# yard-ice-fpga.net
KiCad netlist of a schematic drawn in Altium Designer
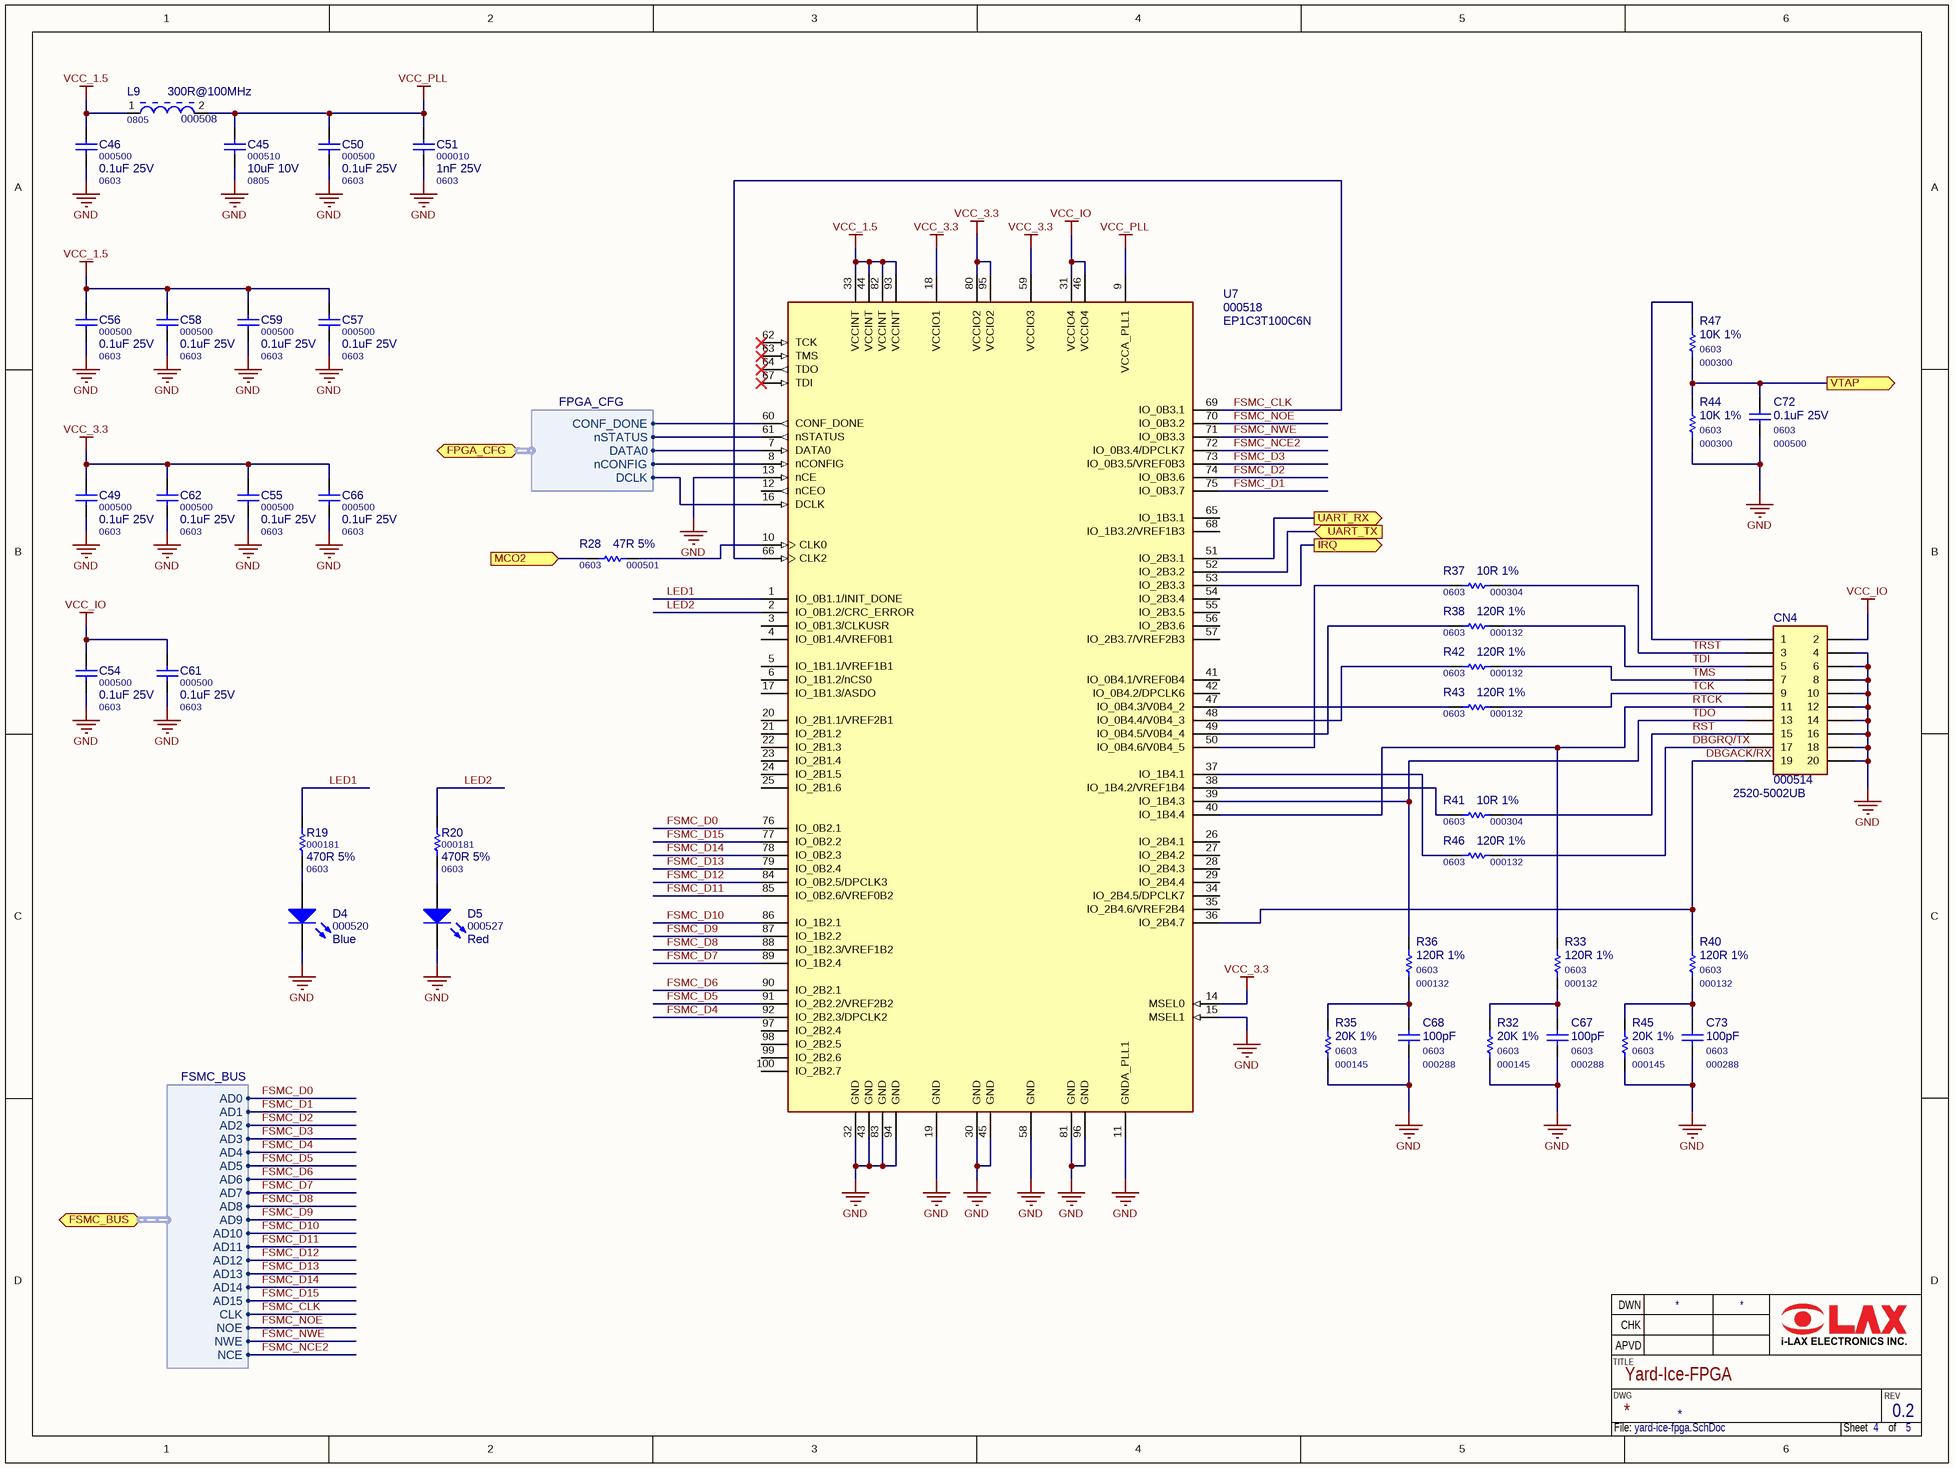
[diagram p0: yard-ice-fpga.SchDoc]

(export (version "E")
  (design (tool "Eeschema 10.0.6"))
  (components
    (comp (ref "C45")
      (value "000510")
      (footprint "C0805M")
      (description "SMD Ceramic Chip Capacitor - 0805 - X7R")
      (fields
        (field (name "ALTIUM_VALUE") "10uF 10V")
        (field (name "PACKAGE") "0805")
        (field (name "MF") "TDK")
      )
      (libsource (lib "discrete-sm") (part "C0805"))
    )
    (comp (ref "C46")
      (value "000500")
      (footprint "C0603M")
      (description "SMD Ceramic Chip Capacitor - 0603 - X7R")
      (fields
        (field (name "ALTIUM_VALUE") "0.1uF 25V")
        (field (name "PACKAGE") "0603")
        (field (name "MF") "TDK")
      )
      (libsource (lib "discrete-sm") (part "C0603"))
    )
    (comp (ref "C49")
      (value "000500")
      (footprint "C0603M")
      (description "SMD Ceramic Chip Capacitor - 0603 - X7R")
      (fields
        (field (name "ALTIUM_VALUE") "0.1uF 25V")
        (field (name "PACKAGE") "0603")
        (field (name "MF") "TDK")
      )
      (libsource (lib "discrete-sm") (part "C0603"))
    )
    (comp (ref "C50")
      (value "000500")
      (footprint "C0603M")
      (description "SMD Ceramic Chip Capacitor - 0603 - X7R")
      (fields
        (field (name "ALTIUM_VALUE") "0.1uF 25V")
        (field (name "PACKAGE") "0603")
        (field (name "MF") "TDK")
      )
      (libsource (lib "discrete-sm") (part "C0603"))
    )
    (comp (ref "C51")
      (value "000010")
      (footprint "C0603M")
      (description "SMD Ceramic Chip Capacitor - 0603 - X7R")
      (fields (field (name "ALTIUM_VALUE") "1nF 25V") (field (name "PACKAGE") "0603"))
      (libsource (lib "discrete-sm") (part "C0603"))
    )
    (comp (ref "C54")
      (value "000500")
      (footprint "C0603M")
      (description "SMD Ceramic Chip Capacitor - 0603 - X7R")
      (fields
        (field (name "ALTIUM_VALUE") "0.1uF 25V")
        (field (name "PACKAGE") "0603")
        (field (name "MF") "TDK")
      )
      (libsource (lib "discrete-sm") (part "C0603"))
    )
    (comp (ref "C55")
      (value "000500")
      (footprint "C0603M")
      (description "SMD Ceramic Chip Capacitor - 0603 - X7R")
      (fields
        (field (name "ALTIUM_VALUE") "0.1uF 25V")
        (field (name "PACKAGE") "0603")
        (field (name "MF") "TDK")
      )
      (libsource (lib "discrete-sm") (part "C0603"))
    )
    (comp (ref "C56")
      (value "000500")
      (footprint "C0603M")
      (description "SMD Ceramic Chip Capacitor - 0603 - X7R")
      (fields
        (field (name "ALTIUM_VALUE") "0.1uF 25V")
        (field (name "PACKAGE") "0603")
        (field (name "MF") "TDK")
      )
      (libsource (lib "discrete-sm") (part "C0603"))
    )
    (comp (ref "C57")
      (value "000500")
      (footprint "C0603M")
      (description "SMD Ceramic Chip Capacitor - 0603 - X7R")
      (fields
        (field (name "ALTIUM_VALUE") "0.1uF 25V")
        (field (name "PACKAGE") "0603")
        (field (name "MF") "TDK")
      )
      (libsource (lib "discrete-sm") (part "C0603"))
    )
    (comp (ref "C58")
      (value "000500")
      (footprint "C0603M")
      (description "SMD Ceramic Chip Capacitor - 0603 - X7R")
      (fields
        (field (name "ALTIUM_VALUE") "0.1uF 25V")
        (field (name "PACKAGE") "0603")
        (field (name "MF") "TDK")
      )
      (libsource (lib "discrete-sm") (part "C0603"))
    )
    (comp (ref "C59")
      (value "000500")
      (footprint "C0603M")
      (description "SMD Ceramic Chip Capacitor - 0603 - X7R")
      (fields
        (field (name "ALTIUM_VALUE") "0.1uF 25V")
        (field (name "PACKAGE") "0603")
        (field (name "MF") "TDK")
      )
      (libsource (lib "discrete-sm") (part "C0603"))
    )
    (comp (ref "C61")
      (value "000500")
      (footprint "C0603M")
      (description "SMD Ceramic Chip Capacitor - 0603 - X7R")
      (fields
        (field (name "ALTIUM_VALUE") "0.1uF 25V")
        (field (name "PACKAGE") "0603")
        (field (name "MF") "TDK")
      )
      (libsource (lib "discrete-sm") (part "C0603"))
    )
    (comp (ref "C62")
      (value "000500")
      (footprint "C0603M")
      (description "SMD Ceramic Chip Capacitor - 0603 - X7R")
      (fields
        (field (name "ALTIUM_VALUE") "0.1uF 25V")
        (field (name "PACKAGE") "0603")
        (field (name "MF") "TDK")
      )
      (libsource (lib "discrete-sm") (part "C0603"))
    )
    (comp (ref "C66")
      (value "000500")
      (footprint "C0603M")
      (description "SMD Ceramic Chip Capacitor - 0603 - X7R")
      (fields
        (field (name "ALTIUM_VALUE") "0.1uF 25V")
        (field (name "PACKAGE") "0603")
        (field (name "MF") "TDK")
      )
      (libsource (lib "discrete-sm") (part "C0603"))
    )
    (comp (ref "C67")
      (value "000288")
      (footprint "C0603M")
      (description "SMD Ceramic Chip Capacitor - 0603")
      (fields (field (name "ALTIUM_VALUE") "100pF") (field (name "PACKAGE") "0603"))
      (libsource (lib "discrete-sm") (part "C0603"))
    )
    (comp (ref "C68")
      (value "000288")
      (footprint "C0603M")
      (description "SMD Ceramic Chip Capacitor - 0603")
      (fields (field (name "ALTIUM_VALUE") "100pF") (field (name "PACKAGE") "0603"))
      (libsource (lib "discrete-sm") (part "C0603"))
    )
    (comp (ref "C72")
      (value "000500")
      (footprint "C0603M")
      (description "SMD Ceramic Chip Capacitor - 0603 - X7R")
      (fields
        (field (name "ALTIUM_VALUE") "0.1uF 25V")
        (field (name "PACKAGE") "0603")
        (field (name "MF") "TDK")
      )
      (libsource (lib "discrete-sm") (part "C0603"))
    )
    (comp (ref "C73")
      (value "000288")
      (footprint "C0603M")
      (description "SMD Ceramic Chip Capacitor - 0603")
      (fields (field (name "ALTIUM_VALUE") "100pF") (field (name "PACKAGE") "0603"))
      (libsource (lib "discrete-sm") (part "C0603"))
    )
    (comp (ref "CN4")
      (value "000514")
      (footprint "TST-110-04-G-D-RA")
      (description "Shrouded Header, 20 Pos, Right Angle")
      (fields (field (name "ALTIUM_VALUE") "2520-5002UB") (field (name "MF") "3M"))
      (libsource (lib "samtec-board-to-board") (part "Header 10X2"))
    )
    (comp (ref "D4")
      (value "000520")
      (footprint "LED0805L LP")
      (description "LED SMD 0805")
      (fields (field (name "ALTIUM_VALUE") "Blue"))
      (libsource (lib "discrete-sm") (part "LED0805LP"))
    )
    (comp (ref "D5")
      (value "000527")
      (footprint "LED0805L LP")
      (description "LED SMD 0805")
      (fields (field (name "ALTIUM_VALUE") "Red"))
      (libsource (lib "discrete-sm") (part "LED0805LP"))
    )
    (comp (ref "L9")
      (value "000508")
      (footprint "L0805M")
      (description "SMD Ferrite Bead 0805")
      (fields
        (field (name "ALTIUM_VALUE") "300R@100MHz")
        (field (name "PACKAGE") "0805")
        (field (name "MF") "TDK")
      )
      (libsource (lib "discrete-sm") (part "L0805"))
    )
    (comp (ref "R19")
      (value "000181")
      (footprint "R0603M")
      (description "SMD Chip Resistor - 0603")
      (fields (field (name "ALTIUM_VALUE") "470R 5%") (field (name "PACKAGE") "0603"))
      (libsource (lib "discrete-sm") (part "R0603"))
    )
    (comp (ref "R20")
      (value "000181")
      (footprint "R0603M")
      (description "SMD Chip Resistor - 0603")
      (fields (field (name "ALTIUM_VALUE") "470R 5%") (field (name "PACKAGE") "0603"))
      (libsource (lib "discrete-sm") (part "R0603"))
    )
    (comp (ref "R28")
      (value "000501")
      (footprint "R0603M")
      (description "SMD Chip Resistor - 0603")
      (fields (field (name "ALTIUM_VALUE") "47R 5%") (field (name "PACKAGE") "0603"))
      (libsource (lib "discrete-sm") (part "R0603"))
    )
    (comp (ref "R32")
      (value "000145")
      (footprint "R0603M")
      (description "SMD Chip Resistor - 0603")
      (fields (field (name "ALTIUM_VALUE") "20K 1%") (field (name "PACKAGE") "0603"))
      (libsource (lib "discrete-sm") (part "R0603"))
    )
    (comp (ref "R33")
      (value "000132")
      (footprint "R0603M")
      (description "SMD Chip Resistor - 0603")
      (fields (field (name "ALTIUM_VALUE") "120R 1%") (field (name "PACKAGE") "0603"))
      (libsource (lib "discrete-sm") (part "R0603"))
    )
    (comp (ref "R35")
      (value "000145")
      (footprint "R0603M")
      (description "SMD Chip Resistor - 0603")
      (fields (field (name "ALTIUM_VALUE") "20K 1%") (field (name "PACKAGE") "0603"))
      (libsource (lib "discrete-sm") (part "R0603"))
    )
    (comp (ref "R36")
      (value "000132")
      (footprint "R0603M")
      (description "SMD Chip Resistor - 0603")
      (fields (field (name "ALTIUM_VALUE") "120R 1%") (field (name "PACKAGE") "0603"))
      (libsource (lib "discrete-sm") (part "R0603"))
    )
    (comp (ref "R37")
      (value "000304")
      (footprint "R0603M")
      (description "SMD Chip Resistor - 0603")
      (fields (field (name "ALTIUM_VALUE") "10R 1%") (field (name "PACKAGE") "0603"))
      (libsource (lib "discrete-sm") (part "R0603"))
    )
    (comp (ref "R38")
      (value "000132")
      (footprint "R0603M")
      (description "SMD Chip Resistor - 0603")
      (fields (field (name "ALTIUM_VALUE") "120R 1%") (field (name "PACKAGE") "0603"))
      (libsource (lib "discrete-sm") (part "R0603"))
    )
    (comp (ref "R40")
      (value "000132")
      (footprint "R0603M")
      (description "SMD Chip Resistor - 0603")
      (fields (field (name "ALTIUM_VALUE") "120R 1%") (field (name "PACKAGE") "0603"))
      (libsource (lib "discrete-sm") (part "R0603"))
    )
    (comp (ref "R41")
      (value "000304")
      (footprint "R0603M")
      (description "SMD Chip Resistor - 0603")
      (fields (field (name "ALTIUM_VALUE") "10R 1%") (field (name "PACKAGE") "0603"))
      (libsource (lib "discrete-sm") (part "R0603"))
    )
    (comp (ref "R42")
      (value "000132")
      (footprint "R0603M")
      (description "SMD Chip Resistor - 0603")
      (fields (field (name "ALTIUM_VALUE") "120R 1%") (field (name "PACKAGE") "0603"))
      (libsource (lib "discrete-sm") (part "R0603"))
    )
    (comp (ref "R43")
      (value "000132")
      (footprint "R0603M")
      (description "SMD Chip Resistor - 0603")
      (fields (field (name "ALTIUM_VALUE") "120R 1%") (field (name "PACKAGE") "0603"))
      (libsource (lib "discrete-sm") (part "R0603"))
    )
    (comp (ref "R44")
      (value "000300")
      (footprint "R0603M")
      (description "SMD Chip Resistor - 0603")
      (fields (field (name "ALTIUM_VALUE") "10K 1%") (field (name "PACKAGE") "0603"))
      (libsource (lib "discrete-sm") (part "R0603"))
    )
    (comp (ref "R45")
      (value "000145")
      (footprint "R0603M")
      (description "SMD Chip Resistor - 0603")
      (fields (field (name "ALTIUM_VALUE") "20K 1%") (field (name "PACKAGE") "0603"))
      (libsource (lib "discrete-sm") (part "R0603"))
    )
    (comp (ref "R46")
      (value "000132")
      (footprint "R0603M")
      (description "SMD Chip Resistor - 0603")
      (fields (field (name "ALTIUM_VALUE") "120R 1%") (field (name "PACKAGE") "0603"))
      (libsource (lib "discrete-sm") (part "R0603"))
    )
    (comp (ref "R47")
      (value "000300")
      (footprint "R0603M")
      (description "SMD Chip Resistor - 0603")
      (fields (field (name "ALTIUM_VALUE") "10K 1%") (field (name "PACKAGE") "0603"))
      (libsource (lib "discrete-sm") (part "R0603"))
    )
    (comp (ref "U7")
      (value "000518")
      (footprint "TQFP-100")
      (description "Cyclone FPGA")
      (fields (field (name "ALTIUM_VALUE") "EP1C3T100C6N") (field (name "MF") "Altera"))
      (libsource (lib "altera-cyclone") (part "EP1C3T100C8N"))
    )
  )
  (nets
    (net (code "3") (name "/CONF_DONE") (class "Default")
      (node (ref "U7") (pin "60") (pinfunction "CONF_DONE_60") (pintype "output"))
    )
    (net (code "4") (name "/DATA0") (class "Default")
      (node (ref "U7") (pin "7") (pinfunction "DATA0_7") (pintype "input"))
    )
    (net (code "5") (name "/DBGACK{slash}RX") (class "Default")
      (node (ref "CN4") (pin "19") (pinfunction "19_19") (pintype "passive"))
      (node (ref "R40") (pin "1") (pinfunction "1_1") (pintype "passive"))
      (node (ref "U7") (pin "36") (pinfunction "IO_2B4.7_36") (pintype "tri_state"))
    )
    (net (code "6") (name "/DBGRQ{slash}TX") (class "Default")
      (node (ref "CN4") (pin "17") (pinfunction "17_17") (pintype "passive"))
      (node (ref "R46") (pin "1") (pinfunction "1_1") (pintype "passive"))
    )
    (net (code "7") (name "/DCLK") (class "Default")
      (node (ref "U7") (pin "16") (pinfunction "DCLK_16") (pintype "input"))
    )
    (net (code "8") (name "/FSMC_CLK") (class "Default")
      (node (ref "U7") (pin "66") (pinfunction "CLK2_66") (pintype "input"))
      (node (ref "U7") (pin "69") (pinfunction "IO_0B3.1_69") (pintype "tri_state"))
    )
    (net (code "9") (name "/FSMC_D0") (class "Default")
      (node (ref "U7") (pin "76") (pinfunction "IO_0B2.1_76") (pintype "tri_state"))
    )
    (net (code "10") (name "/FSMC_D1") (class "Default")
      (node (ref "U7") (pin "75") (pinfunction "IO_0B3.7_75") (pintype "tri_state"))
    )
    (net (code "11") (name "/FSMC_D2") (class "Default")
      (node (ref "U7") (pin "74") (pinfunction "IO_0B3.6_74") (pintype "tri_state"))
    )
    (net (code "12") (name "/FSMC_D3") (class "Default")
      (node (ref "U7") (pin "73") (pinfunction "IO_0B3.5/VREF0B3_73") (pintype "tri_state"))
    )
    (net (code "13") (name "/FSMC_D4") (class "Default")
      (node (ref "U7") (pin "92") (pinfunction "IO_2B2.3/DPCLK2_92") (pintype "tri_state"))
    )
    (net (code "14") (name "/FSMC_D5") (class "Default")
      (node (ref "U7") (pin "91") (pinfunction "IO_2B2.2/VREF2B2_91") (pintype "tri_state"))
    )
    (net (code "15") (name "/FSMC_D6") (class "Default")
      (node (ref "U7") (pin "90") (pinfunction "IO_2B2.1_90") (pintype "tri_state"))
    )
    (net (code "16") (name "/FSMC_D7") (class "Default")
      (node (ref "U7") (pin "89") (pinfunction "IO_1B2.4_89") (pintype "tri_state"))
    )
    (net (code "17") (name "/FSMC_D8") (class "Default")
      (node (ref "U7") (pin "88") (pinfunction "IO_1B2.3/VREF1B2_88") (pintype "tri_state"))
    )
    (net (code "18") (name "/FSMC_D9") (class "Default")
      (node (ref "U7") (pin "87") (pinfunction "IO_1B2.2_87") (pintype "tri_state"))
    )
    (net (code "19") (name "/FSMC_D10") (class "Default")
      (node (ref "U7") (pin "86") (pinfunction "IO_1B2.1_86") (pintype "tri_state"))
    )
    (net (code "20") (name "/FSMC_D11") (class "Default")
      (node (ref "U7") (pin "85") (pinfunction "IO_0B2.6/VREF0B2_85") (pintype "tri_state"))
    )
    (net (code "21") (name "/FSMC_D12") (class "Default")
      (node (ref "U7") (pin "84") (pinfunction "IO_0B2.5/DPCLK3_84") (pintype "tri_state"))
    )
    (net (code "22") (name "/FSMC_D13") (class "Default")
      (node (ref "U7") (pin "79") (pinfunction "IO_0B2.4_79") (pintype "tri_state"))
    )
    (net (code "23") (name "/FSMC_D14") (class "Default")
      (node (ref "U7") (pin "78") (pinfunction "IO_0B2.3_78") (pintype "tri_state"))
    )
    (net (code "24") (name "/FSMC_D15") (class "Default")
      (node (ref "U7") (pin "77") (pinfunction "IO_0B2.2_77") (pintype "tri_state"))
    )
    (net (code "25") (name "/FSMC_NCE2") (class "Default")
      (node (ref "U7") (pin "72") (pinfunction "IO_0B3.4/DPCLK7_72") (pintype "tri_state"))
    )
    (net (code "26") (name "/FSMC_NOE") (class "Default")
      (node (ref "U7") (pin "70") (pinfunction "IO_0B3.2_70") (pintype "tri_state"))
    )
    (net (code "27") (name "/FSMC_NWE") (class "Default")
      (node (ref "U7") (pin "71") (pinfunction "IO_0B3.3_71") (pintype "tri_state"))
    )
    (net (code "28") (name "/IRQ") (class "Default")
      (node (ref "U7") (pin "53") (pinfunction "IO_2B3.3_53") (pintype "tri_state"))
    )
    (net (code "29") (name "/LED1") (class "Default")
      (node (ref "R19") (pin "1") (pinfunction "1_1") (pintype "passive"))
      (node (ref "U7") (pin "1") (pinfunction "IO_0B1.1/INIT_DONE_1") (pintype "tri_state"))
    )
    (net (code "30") (name "/LED2") (class "Default")
      (node (ref "R20") (pin "1") (pinfunction "1_1") (pintype "passive"))
      (node (ref "U7") (pin "2") (pinfunction "IO_0B1.2/CRC_ERROR_2") (pintype "tri_state"))
    )
    (net (code "31") (name "/MCO2") (class "Default")
      (node (ref "R28") (pin "2") (pinfunction "2_2") (pintype "passive"))
    )
    (net (code "32") (name "/RST") (class "Default")
      (node (ref "CN4") (pin "15") (pinfunction "15_15") (pintype "passive"))
      (node (ref "R41") (pin "1") (pinfunction "1_1") (pintype "passive"))
    )
    (net (code "33") (name "/RTCK") (class "Default")
      (node (ref "CN4") (pin "11") (pinfunction "11_11") (pintype "passive"))
      (node (ref "R33") (pin "1") (pinfunction "1_1") (pintype "passive"))
      (node (ref "U7") (pin "40") (pinfunction "IO_1B4.4_40") (pintype "tri_state"))
    )
    (net (code "34") (name "/TCK") (class "Default")
      (node (ref "CN4") (pin "9") (pinfunction "9_9") (pintype "passive"))
      (node (ref "R43") (pin "1") (pinfunction "1_1") (pintype "passive"))
    )
    (net (code "35") (name "/TDI") (class "Default")
      (node (ref "CN4") (pin "5") (pinfunction "5_5") (pintype "passive"))
      (node (ref "R38") (pin "1") (pinfunction "1_1") (pintype "passive"))
    )
    (net (code "36") (name "/TDO") (class "Default")
      (node (ref "CN4") (pin "13") (pinfunction "13_13") (pintype "passive"))
      (node (ref "R36") (pin "1") (pinfunction "1_1") (pintype "passive"))
      (node (ref "U7") (pin "39") (pinfunction "IO_1B4.3_39") (pintype "tri_state"))
    )
    (net (code "37") (name "/TMS") (class "Default")
      (node (ref "CN4") (pin "7") (pinfunction "7_7") (pintype "passive"))
      (node (ref "R42") (pin "1") (pinfunction "1_1") (pintype "passive"))
    )
    (net (code "38") (name "/TRST") (class "Default")
      (node (ref "CN4") (pin "3") (pinfunction "3_3") (pintype "passive"))
      (node (ref "R37") (pin "1") (pinfunction "1_1") (pintype "passive"))
    )
    (net (code "39") (name "/UART_RX") (class "Default")
      (node (ref "U7") (pin "51") (pinfunction "IO_2B3.1_51") (pintype "tri_state"))
    )
    (net (code "40") (name "/UART_TX") (class "Default")
      (node (ref "U7") (pin "52") (pinfunction "IO_2B3.2_52") (pintype "tri_state"))
    )
    (net (code "41") (name "/VTAP") (class "Default")
      (node (ref "C72") (pin "1") (pinfunction "1_1") (pintype "passive"))
      (node (ref "R44") (pin "1") (pinfunction "1_1") (pintype "passive"))
      (node (ref "R47") (pin "2") (pinfunction "2_2") (pintype "passive"))
    )
    (net (code "42") (name "/nCONFIG") (class "Default")
      (node (ref "U7") (pin "8") (pinfunction "nCONFIG_8") (pintype "input"))
    )
    (net (code "43") (name "/nSTATUS") (class "Default")
      (node (ref "U7") (pin "61") (pinfunction "nSTATUS_61") (pintype "output"))
    )
    (net (code "46") (name "GND") (class "Default")
      (node (ref "C45") (pin "2") (pinfunction "2_2") (pintype "passive"))
      (node (ref "C46") (pin "2") (pinfunction "2_2") (pintype "passive"))
      (node (ref "C49") (pin "2") (pinfunction "2_2") (pintype "passive"))
      (node (ref "C50") (pin "2") (pinfunction "2_2") (pintype "passive"))
      (node (ref "C51") (pin "2") (pinfunction "2_2") (pintype "passive"))
      (node (ref "C54") (pin "2") (pinfunction "2_2") (pintype "passive"))
      (node (ref "C55") (pin "2") (pinfunction "2_2") (pintype "passive"))
      (node (ref "C56") (pin "2") (pinfunction "2_2") (pintype "passive"))
      (node (ref "C57") (pin "2") (pinfunction "2_2") (pintype "passive"))
      (node (ref "C58") (pin "2") (pinfunction "2_2") (pintype "passive"))
      (node (ref "C59") (pin "2") (pinfunction "2_2") (pintype "passive"))
      (node (ref "C61") (pin "2") (pinfunction "2_2") (pintype "passive"))
      (node (ref "C62") (pin "2") (pinfunction "2_2") (pintype "passive"))
      (node (ref "C66") (pin "2") (pinfunction "2_2") (pintype "passive"))
      (node (ref "C67") (pin "2") (pinfunction "2_2") (pintype "passive"))
      (node (ref "C68") (pin "2") (pinfunction "2_2") (pintype "passive"))
      (node (ref "C72") (pin "2") (pinfunction "2_2") (pintype "passive"))
      (node (ref "C73") (pin "2") (pinfunction "2_2") (pintype "passive"))
      (node (ref "CN4") (pin "10") (pinfunction "10_10") (pintype "passive"))
      (node (ref "CN4") (pin "12") (pinfunction "12_12") (pintype "passive"))
      (node (ref "CN4") (pin "14") (pinfunction "14_14") (pintype "passive"))
      (node (ref "CN4") (pin "16") (pinfunction "16_16") (pintype "passive"))
      (node (ref "CN4") (pin "18") (pinfunction "18_18") (pintype "passive"))
      (node (ref "CN4") (pin "20") (pinfunction "20_20") (pintype "passive"))
      (node (ref "CN4") (pin "4") (pinfunction "4_4") (pintype "passive"))
      (node (ref "CN4") (pin "6") (pinfunction "6_6") (pintype "passive"))
      (node (ref "CN4") (pin "8") (pinfunction "8_8") (pintype "passive"))
      (node (ref "D4") (pin "2") (pinfunction "K_2") (pintype "passive"))
      (node (ref "D5") (pin "2") (pinfunction "K_2") (pintype "passive"))
      (node (ref "R32") (pin "2") (pinfunction "2_2") (pintype "passive"))
      (node (ref "R35") (pin "2") (pinfunction "2_2") (pintype "passive"))
      (node (ref "R44") (pin "2") (pinfunction "2_2") (pintype "passive"))
      (node (ref "R45") (pin "2") (pinfunction "2_2") (pintype "passive"))
      (node (ref "U7") (pin "11") (pinfunction "GNDA_PLL1_11") (pintype "power_in"))
      (node (ref "U7") (pin "13") (pinfunction "nCE_13") (pintype "input"))
      (node (ref "U7") (pin "15") (pinfunction "MSEL1_15") (pintype "input"))
      (node (ref "U7") (pin "19") (pinfunction "GND_19") (pintype "power_in"))
      (node (ref "U7") (pin "30") (pinfunction "GND_30") (pintype "power_in"))
      (node (ref "U7") (pin "32") (pinfunction "GND_32") (pintype "power_in"))
      (node (ref "U7") (pin "43") (pinfunction "GND_43") (pintype "power_in"))
      (node (ref "U7") (pin "45") (pinfunction "GND_45") (pintype "power_in"))
      (node (ref "U7") (pin "58") (pinfunction "GND_58") (pintype "power_in"))
      (node (ref "U7") (pin "81") (pinfunction "GND_81") (pintype "power_in"))
      (node (ref "U7") (pin "83") (pinfunction "GND_83") (pintype "power_in"))
      (node (ref "U7") (pin "94") (pinfunction "GND_94") (pintype "power_in"))
      (node (ref "U7") (pin "96") (pinfunction "GND_96") (pintype "power_in"))
    )
    (net (code "47") (name "Net-(C67-Pad1)") (class "Default")
      (node (ref "C67") (pin "1") (pinfunction "1_1") (pintype "passive"))
      (node (ref "R32") (pin "1") (pinfunction "1_1") (pintype "passive"))
      (node (ref "R33") (pin "2") (pinfunction "2_2") (pintype "passive"))
    )
    (net (code "48") (name "Net-(C68-Pad1)") (class "Default")
      (node (ref "C68") (pin "1") (pinfunction "1_1") (pintype "passive"))
      (node (ref "R35") (pin "1") (pinfunction "1_1") (pintype "passive"))
      (node (ref "R36") (pin "2") (pinfunction "2_2") (pintype "passive"))
    )
    (net (code "49") (name "Net-(C73-Pad1)") (class "Default")
      (node (ref "C73") (pin "1") (pinfunction "1_1") (pintype "passive"))
      (node (ref "R40") (pin "2") (pinfunction "2_2") (pintype "passive"))
      (node (ref "R45") (pin "1") (pinfunction "1_1") (pintype "passive"))
    )
    (net (code "50") (name "Net-(CN4-Pad1)") (class "Default")
      (node (ref "CN4") (pin "1") (pinfunction "1_1") (pintype "passive"))
      (node (ref "R47") (pin "1") (pinfunction "1_1") (pintype "passive"))
    )
    (net (code "51") (name "Net-(D4-A)") (class "Default")
      (node (ref "D4") (pin "1") (pinfunction "A_1") (pintype "passive"))
      (node (ref "R19") (pin "2") (pinfunction "2_2") (pintype "passive"))
    )
    (net (code "52") (name "Net-(D5-A)") (class "Default")
      (node (ref "D5") (pin "1") (pinfunction "A_1") (pintype "passive"))
      (node (ref "R20") (pin "2") (pinfunction "2_2") (pintype "passive"))
    )
    (net (code "53") (name "Net-(U7-CLK0)") (class "Default")
      (node (ref "R28") (pin "1") (pinfunction "1_1") (pintype "passive"))
      (node (ref "U7") (pin "10") (pinfunction "CLK0_10") (pintype "input"))
    )
    (net (code "54") (name "Net-(U7-IO_0B4.3{slash}V0B4_2)") (class "Default")
      (node (ref "R43") (pin "2") (pinfunction "2_2") (pintype "passive"))
      (node (ref "U7") (pin "47") (pinfunction "IO_0B4.3/V0B4_2_47") (pintype "tri_state"))
    )
    (net (code "55") (name "Net-(U7-IO_0B4.4{slash}V0B4_3)") (class "Default")
      (node (ref "R42") (pin "2") (pinfunction "2_2") (pintype "passive"))
      (node (ref "U7") (pin "48") (pinfunction "IO_0B4.4/V0B4_3_48") (pintype "tri_state"))
    )
    (net (code "56") (name "Net-(U7-IO_0B4.5{slash}V0B4_4)") (class "Default")
      (node (ref "R38") (pin "2") (pinfunction "2_2") (pintype "passive"))
      (node (ref "U7") (pin "49") (pinfunction "IO_0B4.5/V0B4_4_49") (pintype "tri_state"))
    )
    (net (code "57") (name "Net-(U7-IO_0B4.6{slash}V0B4_5)") (class "Default")
      (node (ref "R37") (pin "2") (pinfunction "2_2") (pintype "passive"))
      (node (ref "U7") (pin "50") (pinfunction "IO_0B4.6/V0B4_5_50") (pintype "tri_state"))
    )
    (net (code "58") (name "Net-(U7-IO_1B4.1)") (class "Default")
      (node (ref "R46") (pin "2") (pinfunction "2_2") (pintype "passive"))
      (node (ref "U7") (pin "37") (pinfunction "IO_1B4.1_37") (pintype "tri_state"))
    )
    (net (code "59") (name "Net-(U7-IO_1B4.2{slash}VREF1B4)") (class "Default")
      (node (ref "R41") (pin "2") (pinfunction "2_2") (pintype "passive"))
      (node (ref "U7") (pin "38") (pinfunction "IO_1B4.2/VREF1B4_38") (pintype "tri_state"))
    )
    (net (code "60") (name "VCC_1.5") (class "Default")
      (node (ref "C46") (pin "1") (pinfunction "1_1") (pintype "passive"))
      (node (ref "C56") (pin "1") (pinfunction "1_1") (pintype "passive"))
      (node (ref "C57") (pin "1") (pinfunction "1_1") (pintype "passive"))
      (node (ref "C58") (pin "1") (pinfunction "1_1") (pintype "passive"))
      (node (ref "C59") (pin "1") (pinfunction "1_1") (pintype "passive"))
      (node (ref "L9") (pin "1") (pinfunction "1_1") (pintype "passive"))
      (node (ref "U7") (pin "33") (pinfunction "VCCINT_33") (pintype "power_in"))
      (node (ref "U7") (pin "44") (pinfunction "VCCINT_44") (pintype "power_in"))
      (node (ref "U7") (pin "82") (pinfunction "VCCINT_82") (pintype "power_in"))
      (node (ref "U7") (pin "93") (pinfunction "VCCINT_93") (pintype "power_in"))
    )
    (net (code "61") (name "VCC_3.3") (class "Default")
      (node (ref "C49") (pin "1") (pinfunction "1_1") (pintype "passive"))
      (node (ref "C55") (pin "1") (pinfunction "1_1") (pintype "passive"))
      (node (ref "C62") (pin "1") (pinfunction "1_1") (pintype "passive"))
      (node (ref "C66") (pin "1") (pinfunction "1_1") (pintype "passive"))
      (node (ref "U7") (pin "14") (pinfunction "MSEL0_14") (pintype "input"))
      (node (ref "U7") (pin "18") (pinfunction "VCCIO1_18") (pintype "power_in"))
      (node (ref "U7") (pin "59") (pinfunction "VCCIO3_59") (pintype "power_in"))
      (node (ref "U7") (pin "80") (pinfunction "VCCIO2_80") (pintype "power_in"))
      (node (ref "U7") (pin "95") (pinfunction "VCCIO2_95") (pintype "power_in"))
    )
    (net (code "62") (name "VCC_IO") (class "Default")
      (node (ref "C54") (pin "1") (pinfunction "1_1") (pintype "passive"))
      (node (ref "C61") (pin "1") (pinfunction "1_1") (pintype "passive"))
      (node (ref "CN4") (pin "2") (pinfunction "2_2") (pintype "passive"))
      (node (ref "U7") (pin "31") (pinfunction "VCCIO4_31") (pintype "power_in"))
      (node (ref "U7") (pin "46") (pinfunction "VCCIO4_46") (pintype "power_in"))
    )
    (net (code "63") (name "VCC_PLL") (class "Default")
      (node (ref "C45") (pin "1") (pinfunction "1_1") (pintype "passive"))
      (node (ref "C50") (pin "1") (pinfunction "1_1") (pintype "passive"))
      (node (ref "C51") (pin "1") (pinfunction "1_1") (pintype "passive"))
      (node (ref "L9") (pin "2") (pinfunction "2_2") (pintype "passive"))
      (node (ref "U7") (pin "9") (pinfunction "VCCA_PLL1_9") (pintype "power_in"))
    )
    (net (code "64") (name "unconnected-(U7-IO_0B1.3{slash}CLKUSR-Pad3)") (class "Default")
      (node (ref "U7") (pin "3") (pinfunction "IO_0B1.3/CLKUSR_3") (pintype "tri_state"))
    )
    (net (code "65") (name "unconnected-(U7-IO_0B1.4{slash}VREF0B1-Pad4)") (class "Default")
      (node (ref "U7") (pin "4") (pinfunction "IO_0B1.4/VREF0B1_4") (pintype "tri_state"))
    )
    (net (code "66") (name "unconnected-(U7-IO_0B4.1{slash}VREF0B4-Pad41)") (class "Default")
      (node (ref "U7") (pin "41") (pinfunction "IO_0B4.1/VREF0B4_41") (pintype "tri_state"))
    )
    (net (code "67") (name "unconnected-(U7-IO_0B4.2{slash}DPCLK6-Pad42)") (class "Default")
      (node (ref "U7") (pin "42") (pinfunction "IO_0B4.2/DPCLK6_42") (pintype "tri_state"))
    )
    (net (code "68") (name "unconnected-(U7-IO_1B1.1{slash}VREF1B1-Pad5)") (class "Default")
      (node (ref "U7") (pin "5") (pinfunction "IO_1B1.1/VREF1B1_5") (pintype "tri_state"))
    )
    (net (code "69") (name "unconnected-(U7-IO_1B1.2{slash}nCS0-Pad6)") (class "Default")
      (node (ref "U7") (pin "6") (pinfunction "IO_1B1.2/nCS0_6") (pintype "tri_state"))
    )
    (net (code "70") (name "unconnected-(U7-IO_1B1.3{slash}ASDO-Pad17)") (class "Default")
      (node (ref "U7") (pin "17") (pinfunction "IO_1B1.3/ASDO_17") (pintype "tri_state"))
    )
    (net (code "71") (name "unconnected-(U7-IO_1B3.1-Pad65)") (class "Default")
      (node (ref "U7") (pin "65") (pinfunction "IO_1B3.1_65") (pintype "tri_state"))
    )
    (net (code "72") (name "unconnected-(U7-IO_1B3.2{slash}VREF1B3-Pad68)") (class "Default")
      (node (ref "U7") (pin "68") (pinfunction "IO_1B3.2/VREF1B3_68") (pintype "tri_state"))
    )
    (net (code "73") (name "unconnected-(U7-IO_2B1.1{slash}VREF2B1-Pad20)") (class "Default")
      (node (ref "U7") (pin "20") (pinfunction "IO_2B1.1/VREF2B1_20") (pintype "tri_state"))
    )
    (net (code "74") (name "unconnected-(U7-IO_2B1.2-Pad21)") (class "Default")
      (node (ref "U7") (pin "21") (pinfunction "IO_2B1.2_21") (pintype "tri_state"))
    )
    (net (code "75") (name "unconnected-(U7-IO_2B1.3-Pad22)") (class "Default")
      (node (ref "U7") (pin "22") (pinfunction "IO_2B1.3_22") (pintype "tri_state"))
    )
    (net (code "76") (name "unconnected-(U7-IO_2B1.4-Pad23)") (class "Default")
      (node (ref "U7") (pin "23") (pinfunction "IO_2B1.4_23") (pintype "tri_state"))
    )
    (net (code "77") (name "unconnected-(U7-IO_2B1.5-Pad24)") (class "Default")
      (node (ref "U7") (pin "24") (pinfunction "IO_2B1.5_24") (pintype "tri_state"))
    )
    (net (code "78") (name "unconnected-(U7-IO_2B1.6-Pad25)") (class "Default")
      (node (ref "U7") (pin "25") (pinfunction "IO_2B1.6_25") (pintype "tri_state"))
    )
    (net (code "79") (name "unconnected-(U7-IO_2B2.4-Pad97)") (class "Default")
      (node (ref "U7") (pin "97") (pinfunction "IO_2B2.4_97") (pintype "tri_state"))
    )
    (net (code "80") (name "unconnected-(U7-IO_2B2.5-Pad98)") (class "Default")
      (node (ref "U7") (pin "98") (pinfunction "IO_2B2.5_98") (pintype "tri_state"))
    )
    (net (code "81") (name "unconnected-(U7-IO_2B2.6-Pad99)") (class "Default")
      (node (ref "U7") (pin "99") (pinfunction "IO_2B2.6_99") (pintype "tri_state"))
    )
    (net (code "82") (name "unconnected-(U7-IO_2B2.7-Pad100)") (class "Default")
      (node (ref "U7") (pin "100") (pinfunction "IO_2B2.7_100") (pintype "tri_state"))
    )
    (net (code "83") (name "unconnected-(U7-IO_2B3.4-Pad54)") (class "Default")
      (node (ref "U7") (pin "54") (pinfunction "IO_2B3.4_54") (pintype "tri_state"))
    )
    (net (code "84") (name "unconnected-(U7-IO_2B3.5-Pad55)") (class "Default")
      (node (ref "U7") (pin "55") (pinfunction "IO_2B3.5_55") (pintype "tri_state"))
    )
    (net (code "85") (name "unconnected-(U7-IO_2B3.6-Pad56)") (class "Default")
      (node (ref "U7") (pin "56") (pinfunction "IO_2B3.6_56") (pintype "tri_state"))
    )
    (net (code "86") (name "unconnected-(U7-IO_2B3.7{slash}VREF2B3-Pad57)") (class "Default")
      (node (ref "U7") (pin "57") (pinfunction "IO_2B3.7/VREF2B3_57") (pintype "tri_state"))
    )
    (net (code "87") (name "unconnected-(U7-IO_2B4.1-Pad26)") (class "Default")
      (node (ref "U7") (pin "26") (pinfunction "IO_2B4.1_26") (pintype "tri_state"))
    )
    (net (code "88") (name "unconnected-(U7-IO_2B4.2-Pad27)") (class "Default")
      (node (ref "U7") (pin "27") (pinfunction "IO_2B4.2_27") (pintype "tri_state"))
    )
    (net (code "89") (name "unconnected-(U7-IO_2B4.3-Pad28)") (class "Default")
      (node (ref "U7") (pin "28") (pinfunction "IO_2B4.3_28") (pintype "tri_state"))
    )
    (net (code "90") (name "unconnected-(U7-IO_2B4.4-Pad29)") (class "Default")
      (node (ref "U7") (pin "29") (pinfunction "IO_2B4.4_29") (pintype "tri_state"))
    )
    (net (code "91") (name "unconnected-(U7-IO_2B4.5{slash}DPCLK7-Pad34)") (class "Default")
      (node (ref "U7") (pin "34") (pinfunction "IO_2B4.5/DPCLK7_34") (pintype "tri_state"))
    )
    (net (code "92") (name "unconnected-(U7-IO_2B4.6{slash}VREF2B4-Pad35)") (class "Default")
      (node (ref "U7") (pin "35") (pinfunction "IO_2B4.6/VREF2B4_35") (pintype "tri_state"))
    )
    (net (code "93") (name "unconnected-(U7-TCK-Pad62)") (class "Default")
      (node (ref "U7") (pin "62") (pinfunction "TCK_62") (pintype "input+no_connect"))
    )
    (net (code "94") (name "unconnected-(U7-TDI-Pad67)") (class "Default")
      (node (ref "U7") (pin "67") (pinfunction "TDI_67") (pintype "input+no_connect"))
    )
    (net (code "95") (name "unconnected-(U7-TDO-Pad64)") (class "Default")
      (node (ref "U7") (pin "64") (pinfunction "TDO_64") (pintype "output+no_connect"))
    )
    (net (code "96") (name "unconnected-(U7-TMS-Pad63)") (class "Default")
      (node (ref "U7") (pin "63") (pinfunction "TMS_63") (pintype "input+no_connect"))
    )
    (net (code "97") (name "unconnected-(U7-nCEO-Pad12)") (class "Default")
      (node (ref "U7") (pin "12") (pinfunction "nCEO_12") (pintype "output"))
    )
  )
)
